# 24_069.net
KiCad netlist of a schematic drawn in Altium Designer
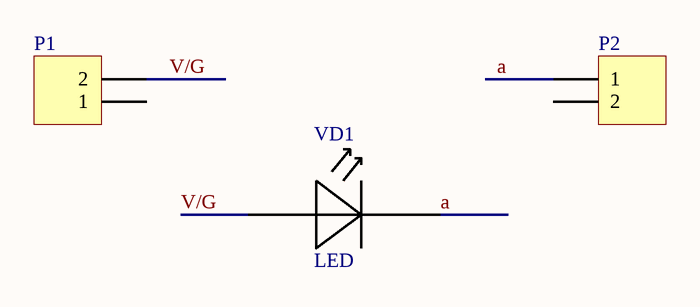
[diagram p0: 24.069.SchDoc]

(export (version "E")
  (design (tool "Eeschema 10.0.6"))
  (components
    (comp (ref "P1")
      (value "Header 2")
      (footprint "HDR1X2")
      (description "Header, 2-Pin")
      (fields (field (name "PUBLISHER") "Altium Limited"))
      (libsource (lib "Miscellaneous Connectors") (part "Header 2"))
    )
    (comp (ref "P2")
      (value "Header 2")
      (footprint "HDR1X2")
      (description "Header, 2-Pin")
      (fields (field (name "PUBLISHER") "Altium Limited"))
      (libsource (lib "") (part "Header 2_1"))
    )
    (comp (ref "VD1") (value "LED") (footprint "LED 24.063") (libsource (lib "msp_SchLib") (part "LED")))
  )
  (nets
    (net (code "1") (name "/V{slash}G") (class "Default")
      (node (ref "P1") (pin "2") (pinfunction "2_2") (pintype "passive"))
      (node (ref "VD1") (pin "1") (pinfunction "1_1") (pintype "passive"))
    )
    (net (code "2") (name "/a") (class "Default")
      (node (ref "P2") (pin "1") (pinfunction "1_1") (pintype "passive"))
      (node (ref "VD1") (pin "2") (pinfunction "2_2") (pintype "passive"))
    )
    (net (code "3") (name "unconnected-(P1-Pad1)") (class "Default")
      (node (ref "P1") (pin "1") (pinfunction "1_1") (pintype "passive"))
    )
    (net (code "4") (name "unconnected-(P2-Pad2)") (class "Default")
      (node (ref "P2") (pin "2") (pinfunction "2_2") (pintype "passive"))
    )
  )
)
